# Tem_sensor_hot_air.net
KiCad netlist of a schematic drawn in Altium Designer
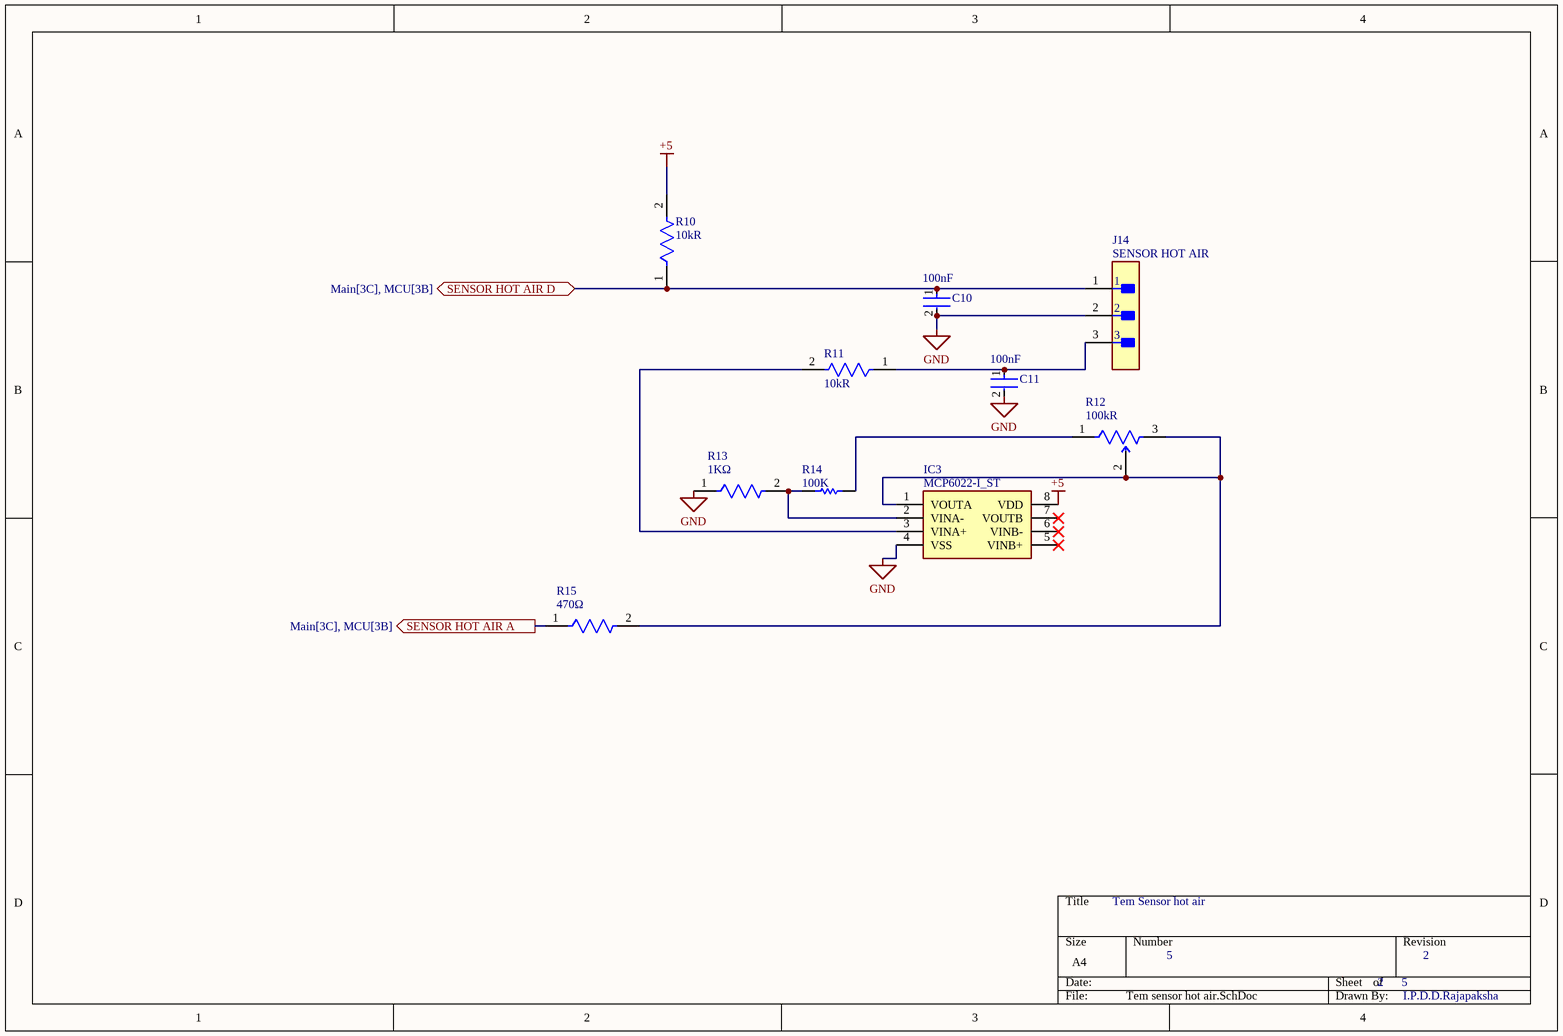
[diagram p0: Tem sensor hot air.SchDoc]

(export (version "E")
  (design (tool "Eeschema 10.0.6"))
  (components
    (comp (ref "C10")
      (value "0805YC104M4T2A")
      (footprint "FP-0805-L_2_01_0_2-W_1_25-IPC_A")
      (description "Automotive Ceramic Capacitor, 0805, 100nF, 20%, X7R, 0.15, 16V")
      (fields (field (name "CAPACITANCE") "100nF") (field (name "TOLERANCE") "20%"))
      (libsource (lib "Altium Content Vault") (part "02cd4be3c70576c341d710602a673aa"))
    )
    (comp (ref "C11")
      (value "0805YC104M4T2A")
      (footprint "FP-0805-L_2_01_0_2-W_1_25-IPC_A")
      (description "Automotive Ceramic Capacitor, 0805, 100nF, 20%, X7R, 0.15, 16V")
      (fields (field (name "CAPACITANCE") "100nF") (field (name "TOLERANCE") "20%"))
      (libsource (lib "Altium Content Vault") (part "02cd4be3c70576c341d710602a673aa"))
    )
    (comp (ref "IC3")
      (value "MCP6022-I_ST")
      (footprint "SamacSys:SOP65P640X120-8N")
      (description "Integrated Circuit")
      (fields
        (field (name "MANUFACTURER_PART_NUMBER") "MCP6022-I/ST")
        (field (name "MOUSER PART NUMBER") "579-MCP6022-I/ST")
      )
      (libsource (lib "*") (part "MCP6022-I_ST"))
    )
    (comp (ref "J14")
      (value "B3B-XH-A(LF)(SN)")
      (footprint "FP-B3B-XH-A_LF_SN-MFG")
      (description "CONN HEADER VERT 3POS 2.5MM")
      (fields (field (name "PARAMETER 1") "SENSOR HOT AIR"))
      (libsource (lib "Altium Content Vault") (part "0d3f023dd272f625e17a2be33dea85f"))
    )
    (comp (ref "R10")
      (value "CRCW120610K0FKEA")
      (footprint "FP-CRCW1206-e3-IPC_C")
      (description "RES Thick Film, 10kΩ, 1%, 0.25W, 100ppm/°C, 1206")
      (fields (field (name "TOLERANCE") "1%") (field (name "RESISTANCE") "10kR"))
      (libsource (lib "Altium Content Vault") (part "1029c3af85768c4190bb7ad29bc67b5"))
    )
    (comp (ref "R11")
      (value "CRCW120610K0FKEA")
      (footprint "FP-CRCW1206-e3-IPC_C")
      (description "RES Thick Film, 10kΩ, 1%, 0.25W, 100ppm/°C, 1206")
      (fields (field (name "TOLERANCE") "1%") (field (name "RESISTANCE") "10kR"))
      (libsource (lib "Altium Content Vault") (part "1029c3af85768c4190bb7ad29bc67b5"))
    )
    (comp (ref "R12")
      (value "67WR100KLF")
      (footprint "FP-67W-MFG")
      (description "TRIMMER 100K OHM 0.5W PC PIN TOP")
      (fields (field (name "RESISTANCE") "100kR") (field (name "TOLERANCE") "10%"))
      (libsource (lib "Altium Content Vault") (part "a77ee20e32664c43a3a1dd5392b6021"))
    )
    (comp (ref "R13")
      (value "1KΩ")
      (footprint "FP-CRGCQ1206-IPC_C")
      (description "CRGCQ1206 1KΩ 0.25W 1% ±100ppm/°C 200V")
      (fields
        (field (name "MANUFACTURER") "TE Connectivity")
        (field (name "MANUFACTURER PART NUMBER") "CRGCQ1206F1K0")
      )
      (libsource (lib "Altium Content Vault") (part "1029c3af85768c4190bb7ad29bc67b5"))
    )
    (comp (ref "R14")
      (value "CRCW1206100KFKEA")
      (footprint "RESC3216X60X45NL10T20")
      (fields (field (name "MANUFACTURER") "Vishay Dale") (field (name "PARAMETER 1") "100K"))
      (libsource (lib "Altium Content Vault") (part "RES"))
    )
    (comp (ref "R15")
      (value "470Ω")
      (footprint "FP-CRGCQ1206-IPC_C")
      (description "CRGCQ 1206 470R 1%")
      (fields
        (field (name "OCTOPART") "https://octopart.com/crgcq1206f470r-te+connectivity-91018284")
        (field (name "MANUFACTURER PART NUMBER") "CRGCQ1206F470R")
      )
      (libsource (lib "Altium Content Vault") (part "1029c3af85768c4190bb7ad29bc67b5"))
    )
  )
  (nets
    (net (code "1") (name "+5") (class "Default")
      (node (ref "IC3") (pin "8") (pinfunction "VDD_8") (pintype "passive"))
      (node (ref "R10") (pin "2") (pinfunction "2_2") (pintype "passive"))
    )
    (net (code "2") (name "/SENSOR HOT AIR A") (class "Default")
      (node (ref "R15") (pin "1") (pinfunction "1_1") (pintype "passive"))
    )
    (net (code "3") (name "/SENSOR HOT AIR D") (class "Default")
      (node (ref "C10") (pin "1") (pinfunction "1_1") (pintype "passive"))
      (node (ref "J14") (pin "1") (pinfunction "1_1") (pintype "passive"))
      (node (ref "R10") (pin "1") (pinfunction "1_1") (pintype "passive"))
    )
    (net (code "4") (name "GND") (class "Default")
      (node (ref "C10") (pin "2") (pinfunction "2_2") (pintype "passive"))
      (node (ref "C11") (pin "2") (pinfunction "2_2") (pintype "passive"))
      (node (ref "IC3") (pin "4") (pinfunction "VSS_4") (pintype "passive"))
      (node (ref "J14") (pin "2") (pinfunction "2_2") (pintype "passive"))
      (node (ref "R13") (pin "1") (pinfunction "1_1") (pintype "passive"))
    )
    (net (code "5") (name "Net-(C11-Pad1)") (class "Default")
      (node (ref "C11") (pin "1") (pinfunction "1_1") (pintype "passive"))
      (node (ref "J14") (pin "3") (pinfunction "3_3") (pintype "passive"))
      (node (ref "R11") (pin "1") (pinfunction "1_1") (pintype "passive"))
    )
    (net (code "6") (name "Net-(IC3-VINA+)") (class "Default")
      (node (ref "IC3") (pin "3") (pinfunction "VINA+_3") (pintype "passive"))
      (node (ref "R11") (pin "2") (pinfunction "2_2") (pintype "passive"))
    )
    (net (code "7") (name "Net-(IC3-VINA-)") (class "Default")
      (node (ref "IC3") (pin "2") (pinfunction "VINA-_2") (pintype "passive"))
      (node (ref "R13") (pin "2") (pinfunction "2_2") (pintype "passive"))
      (node (ref "R14") (pin "1") (pinfunction "1_1") (pintype "passive"))
    )
    (net (code "8") (name "Net-(IC3-VOUTA)") (class "Default")
      (node (ref "IC3") (pin "1") (pinfunction "VOUTA_1") (pintype "passive"))
      (node (ref "R12") (pin "2") (pinfunction "2_2") (pintype "passive"))
      (node (ref "R12") (pin "3") (pinfunction "3_3") (pintype "passive"))
      (node (ref "R15") (pin "2") (pinfunction "2_2") (pintype "passive"))
    )
    (net (code "9") (name "Net-(R12-Pad1)") (class "Default")
      (node (ref "R12") (pin "1") (pinfunction "1_1") (pintype "passive"))
      (node (ref "R14") (pin "2") (pinfunction "2_2") (pintype "passive"))
    )
    (net (code "10") (name "unconnected-(IC3-VINB+-Pad5)") (class "Default")
      (node (ref "IC3") (pin "5") (pinfunction "VINB+_5") (pintype "passive+no_connect"))
    )
    (net (code "11") (name "unconnected-(IC3-VINB--Pad6)") (class "Default")
      (node (ref "IC3") (pin "6") (pinfunction "VINB-_6") (pintype "passive+no_connect"))
    )
    (net (code "12") (name "unconnected-(IC3-VOUTB-Pad7)") (class "Default")
      (node (ref "IC3") (pin "7") (pinfunction "VOUTB_7") (pintype "passive+no_connect"))
    )
  )
)
